# power.net
KiCad netlist of a schematic drawn in Altium Designer
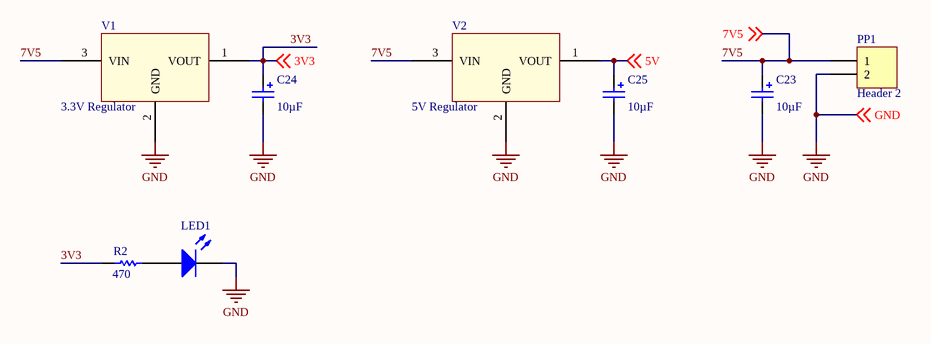
[diagram p0: power.SchDoc]

(export (version "E")
  (design (tool "Eeschema 10.0.6"))
  (components
    (comp (ref "C23")
      (value "10µF")
      (footprint "0805-TC")
      (description "Polarized Capacitor (Radial)")
      (fields (field (name "Comment") "Cap Pol1") (field (name "PUBLISHER") "Altium Limited"))
      (libsource (lib "Miscellaneous Devices") (part "Cap Pol1"))
    )
    (comp (ref "C24")
      (value "10µF")
      (footprint "0805-TC")
      (description "Polarized Capacitor (Radial)")
      (fields (field (name "Comment") "Cap Pol1") (field (name "PUBLISHER") "Altium Limited"))
      (libsource (lib "Miscellaneous Devices") (part "Cap Pol1"))
    )
    (comp (ref "C25")
      (value "10µF")
      (footprint "0805-TC")
      (description "Polarized Capacitor (Radial)")
      (fields (field (name "Comment") "Cap Pol1") (field (name "PUBLISHER") "Altium Limited"))
      (libsource (lib "Miscellaneous Devices") (part "Cap Pol1"))
    )
    (comp (ref "LED1")
      (value "LED2")
      (footprint "0805-LED")
      (description "Typical RED, GREEN, YELLOW, AMBER GaAs LED")
      (fields (field (name "PUBLISHER") "Altium Limited"))
      (libsource (lib "Miscellaneous Devices") (part "LED2"))
    )
    (comp (ref "PP1")
      (value "Header 2")
      (footprint "HDR1X2")
      (description "Header, 2-Pin")
      (fields (field (name "PUBLISHER") "Altium Limited"))
      (libsource (lib "Miscellaneous Connectors") (part "Header 2"))
    )
    (comp (ref "R2")
      (value "470")
      (footprint "0805-R")
      (description "Resistor")
      (fields (field (name "Comment") "Res1") (field (name "PUBLISHER") "Altium Limited"))
      (libsource (lib "Miscellaneous Devices") (part "Res1"))
    )
    (comp (ref "V1")
      (value "3.3V Regulator")
      (footprint "SOT230P700X180-4N")
      (libsource (lib "NCP1117") (part "NCP1117"))
    )
    (comp (ref "V2")
      (value "5V Regulator")
      (footprint "SOT230P700X180-4N")
      (libsource (lib "NCP1117") (part "NCP1117"))
    )
  )
  (nets
    (net (code "1") (name "3V3") (class "Default")
      (node (ref "C24") (pin "1") (pinfunction "1_1") (pintype "passive"))
      (node (ref "R2") (pin "1") (pinfunction "1_1") (pintype "passive"))
      (node (ref "V1") (pin "1") (pinfunction "VOUT_1") (pintype "passive"))
    )
    (net (code "2") (name "5V") (class "Default")
      (node (ref "C25") (pin "1") (pinfunction "1_1") (pintype "passive"))
      (node (ref "V2") (pin "1") (pinfunction "VOUT_1") (pintype "passive"))
    )
    (net (code "3") (name "7V5") (class "Default")
      (node (ref "C23") (pin "1") (pinfunction "1_1") (pintype "passive"))
      (node (ref "PP1") (pin "1") (pinfunction "1_1") (pintype "passive"))
      (node (ref "V1") (pin "3") (pinfunction "VIN_3") (pintype "passive"))
      (node (ref "V2") (pin "3") (pinfunction "VIN_3") (pintype "passive"))
    )
    (net (code "4") (name "GND") (class "Default")
      (node (ref "C23") (pin "2") (pinfunction "2_2") (pintype "passive"))
      (node (ref "C24") (pin "2") (pinfunction "2_2") (pintype "passive"))
      (node (ref "C25") (pin "2") (pinfunction "2_2") (pintype "passive"))
      (node (ref "LED1") (pin "2") (pinfunction "K_2") (pintype "passive"))
      (node (ref "PP1") (pin "2") (pinfunction "2_2") (pintype "passive"))
      (node (ref "V1") (pin "2") (pinfunction "GND_2") (pintype "passive"))
      (node (ref "V2") (pin "2") (pinfunction "GND_2") (pintype "passive"))
    )
    (net (code "5") (name "Net-(LED1-A)") (class "Default")
      (node (ref "LED1") (pin "1") (pinfunction "A_1") (pintype "passive"))
      (node (ref "R2") (pin "2") (pinfunction "2_2") (pintype "passive"))
    )
  )
)
